# board.net
KiCad netlist of a schematic drawn in EAGLE
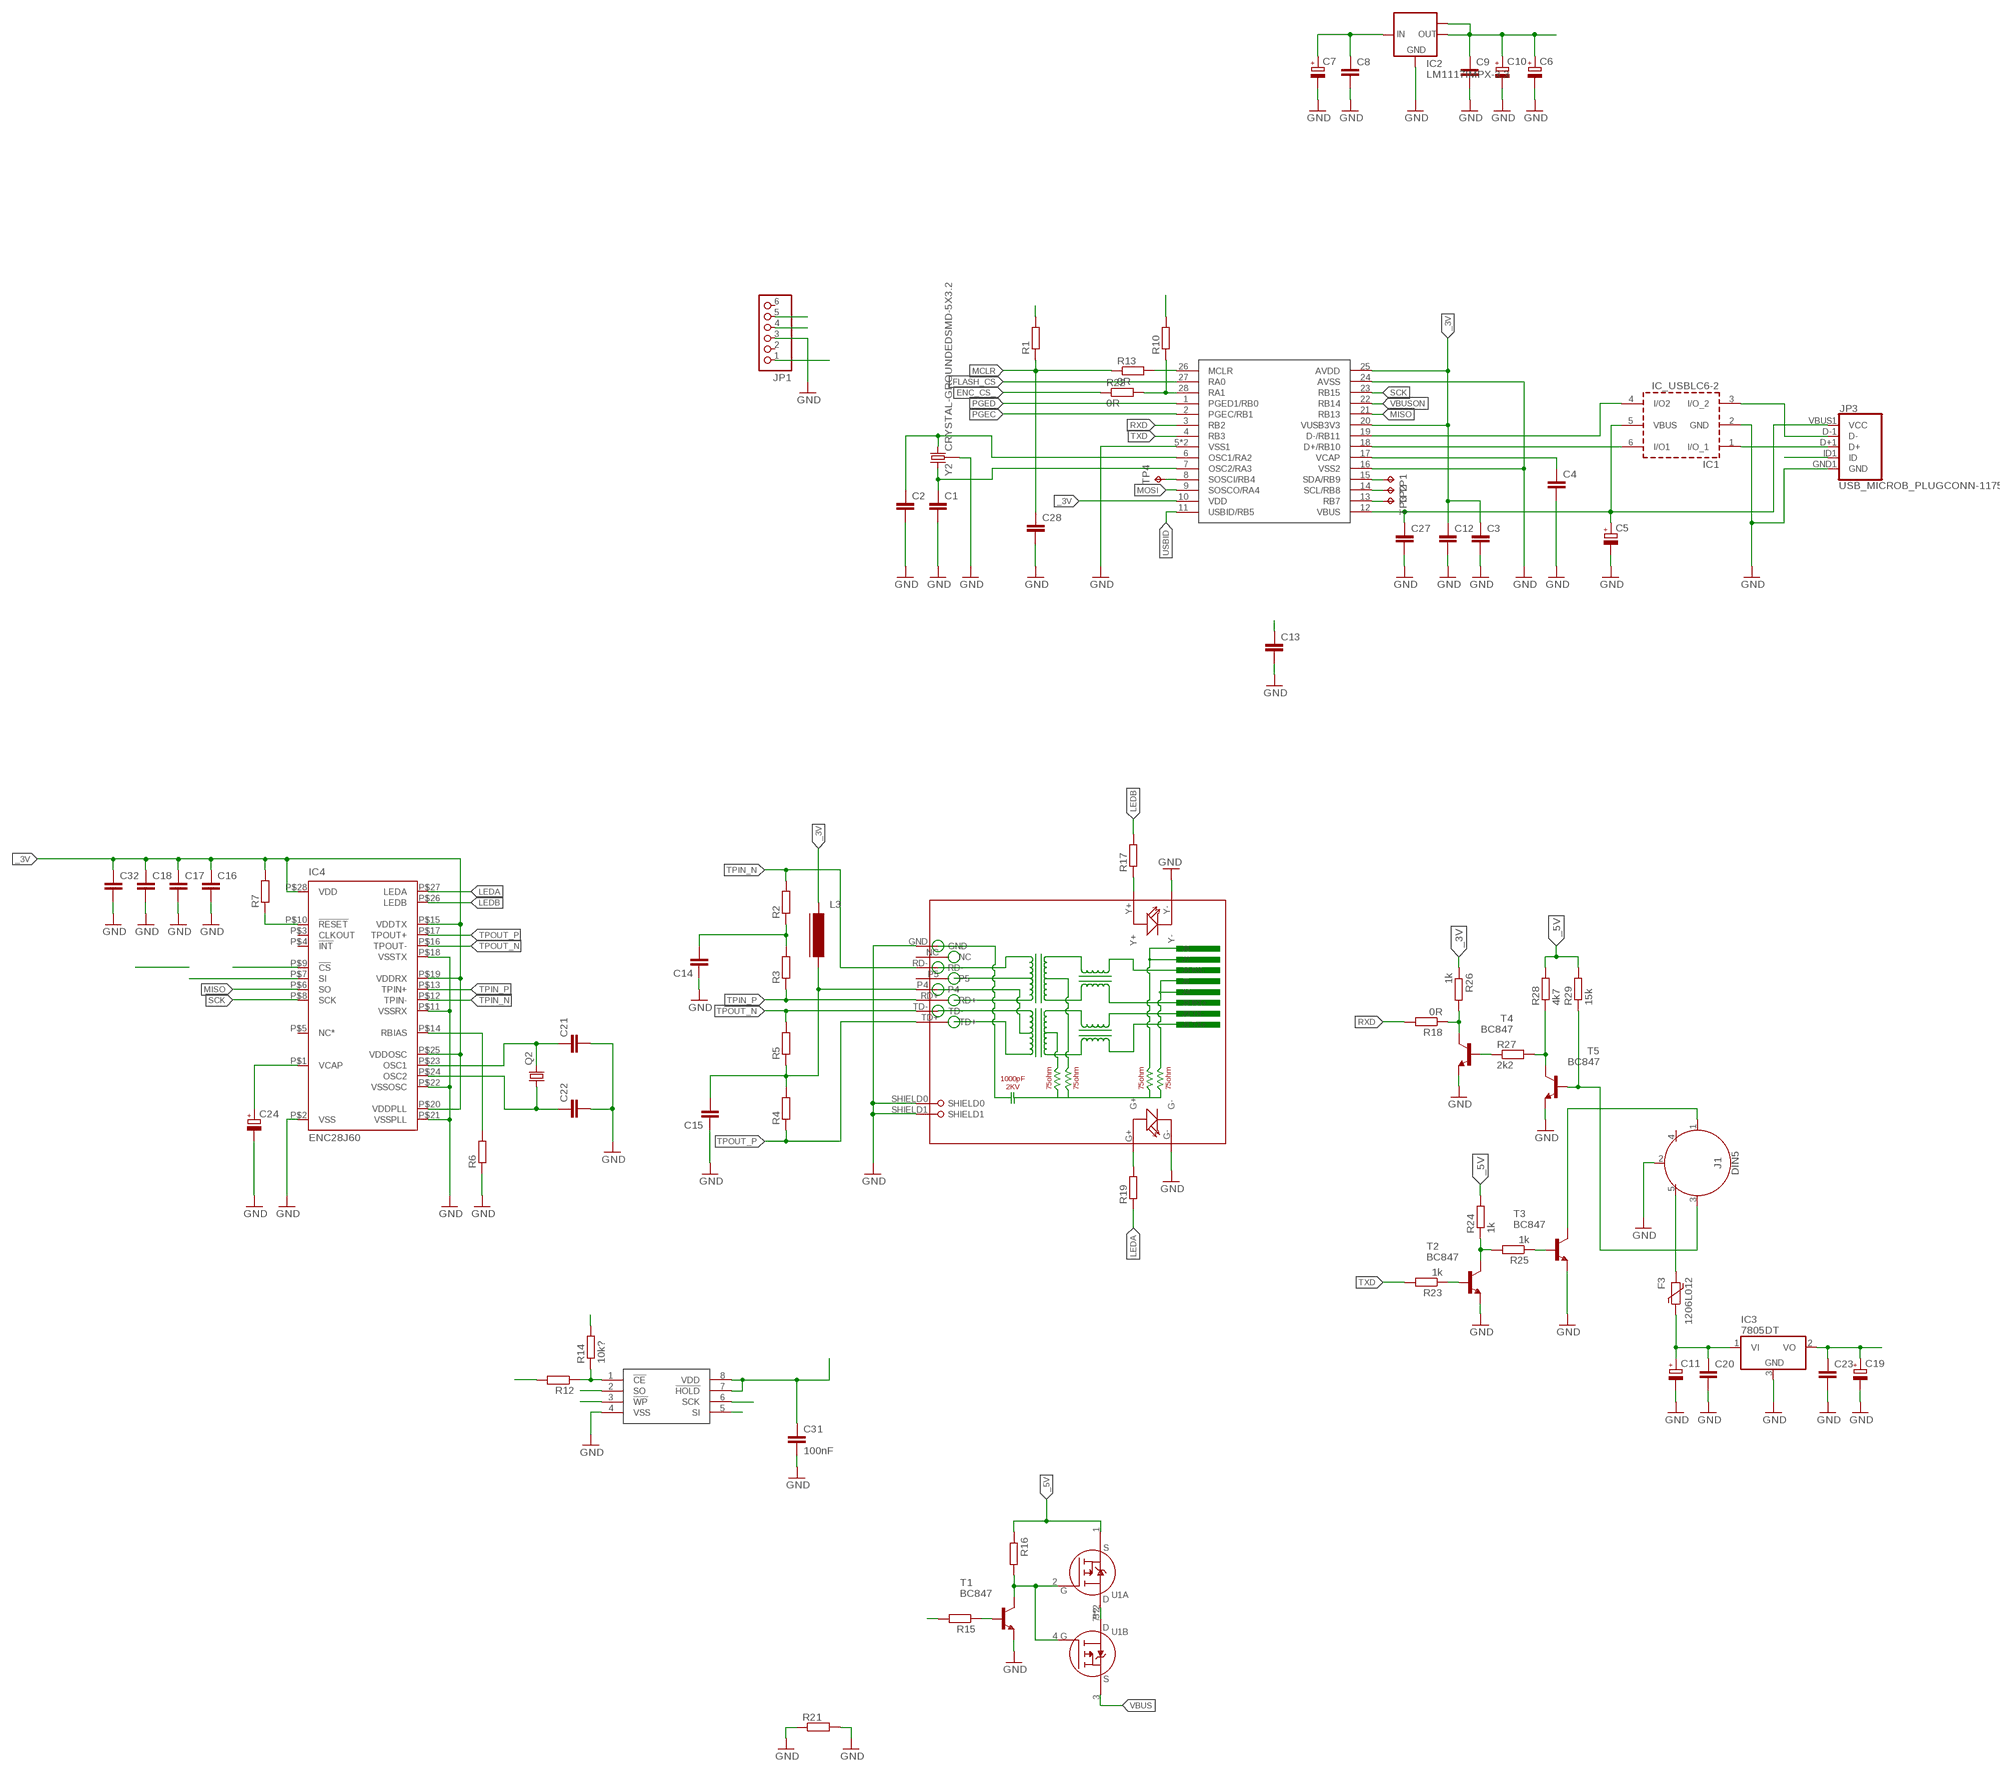
[diagram p0: schematic, sheet 1]

(export (version "E")
  (design (tool "Eeschema 10.0.6"))
  (components
    (comp (ref "C1")
      (value "C-EUC0603")
      (footprint "eagle-import:C0603")
      (libsource (lib "eagle-import") (part "C-EUC0603"))
    )
    (comp (ref "C2")
      (value "C-EUC0603")
      (footprint "eagle-import:C0603")
      (libsource (lib "eagle-import") (part "C-EUC0603"))
    )
    (comp (ref "C3")
      (value "C-EUC0402")
      (footprint "eagle-import:C0402")
      (libsource (lib "eagle-import") (part "C-EUC0402"))
    )
    (comp (ref "C4")
      (value "C-EUC0603")
      (footprint "eagle-import:C0603")
      (libsource (lib "eagle-import") (part "C-EUC0603"))
    )
    (comp (ref "C5")
      (value "CPOL-EUSMCA")
      (footprint "eagle-import:SMC_A")
      (libsource (lib "eagle-import") (part "CPOL-EUSMCA"))
    )
    (comp (ref "C6")
      (value "CPOL-EUSMCA")
      (footprint "eagle-import:SMC_A")
      (libsource (lib "eagle-import") (part "CPOL-EUSMCA"))
    )
    (comp (ref "C7")
      (value "CPOL-EUSMCC")
      (footprint "eagle-import:SMC_C")
      (libsource (lib "eagle-import") (part "CPOL-EUSMCC"))
    )
    (comp (ref "C8")
      (value "C-EUC0603")
      (footprint "eagle-import:C0603")
      (libsource (lib "eagle-import") (part "C-EUC0603"))
    )
    (comp (ref "C9")
      (value "C-EUC0603")
      (footprint "eagle-import:C0603")
      (libsource (lib "eagle-import") (part "C-EUC0603"))
    )
    (comp (ref "C10")
      (value "CPOL-EUSMCB")
      (footprint "eagle-import:SMC_B")
      (libsource (lib "eagle-import") (part "CPOL-EUSMCB"))
    )
    (comp (ref "C11")
      (value "CPOL-EUSMCC")
      (footprint "eagle-import:SMC_C")
      (libsource (lib "eagle-import") (part "CPOL-EUSMCC"))
    )
    (comp (ref "C12")
      (value "C-EUC0603")
      (footprint "eagle-import:C0603")
      (libsource (lib "eagle-import") (part "C-EUC0603"))
    )
    (comp (ref "C13")
      (value "C-EUC0603")
      (footprint "eagle-import:C0603")
      (libsource (lib "eagle-import") (part "C-EUC0603"))
    )
    (comp (ref "C14")
      (value "C-EUC0603")
      (footprint "eagle-import:C0603")
      (libsource (lib "eagle-import") (part "C-EUC0603"))
    )
    (comp (ref "C15")
      (value "C-EUC0603")
      (footprint "eagle-import:C0603")
      (libsource (lib "eagle-import") (part "C-EUC0603"))
    )
    (comp (ref "C16")
      (value "C-EUC0402")
      (footprint "eagle-import:C0402")
      (libsource (lib "eagle-import") (part "C-EUC0402"))
    )
    (comp (ref "C17")
      (value "C-EUC0402")
      (footprint "eagle-import:C0402")
      (libsource (lib "eagle-import") (part "C-EUC0402"))
    )
    (comp (ref "C18")
      (value "C-EUC0402")
      (footprint "eagle-import:C0402")
      (libsource (lib "eagle-import") (part "C-EUC0402"))
    )
    (comp (ref "C19")
      (value "CPOL-EUSMCC")
      (footprint "eagle-import:SMC_C")
      (libsource (lib "eagle-import") (part "CPOL-EUSMCC"))
    )
    (comp (ref "C20")
      (value "C-EUC0603")
      (footprint "eagle-import:C0603")
      (libsource (lib "eagle-import") (part "C-EUC0603"))
    )
    (comp (ref "C21")
      (value "C-EUC0603")
      (footprint "eagle-import:C0603")
      (libsource (lib "eagle-import") (part "C-EUC0603"))
    )
    (comp (ref "C22")
      (value "C-EUC0603")
      (footprint "eagle-import:C0603")
      (libsource (lib "eagle-import") (part "C-EUC0603"))
    )
    (comp (ref "C23")
      (value "C-EUC0603")
      (footprint "eagle-import:C0603")
      (libsource (lib "eagle-import") (part "C-EUC0603"))
    )
    (comp (ref "C24")
      (value "CPOL-EUSMCA")
      (footprint "eagle-import:SMC_A")
      (libsource (lib "eagle-import") (part "CPOL-EUSMCA"))
    )
    (comp (ref "C27")
      (value "C-EUC0603")
      (footprint "eagle-import:C0603")
      (libsource (lib "eagle-import") (part "C-EUC0603"))
    )
    (comp (ref "C28")
      (value "C-EUC0603")
      (footprint "eagle-import:C0603")
      (libsource (lib "eagle-import") (part "C-EUC0603"))
    )
    (comp (ref "C31")
      (value "100nF")
      (footprint "eagle-import:C0603")
      (libsource (lib "eagle-import") (part "C-EUC0603"))
    )
    (comp (ref "C32")
      (value "C-EUC0402")
      (footprint "eagle-import:C0402")
      (libsource (lib "eagle-import") (part "C-EUC0402"))
    )
    (comp (ref "F3")
      (value "1206L012")
      (footprint "eagle-import:1206L")
      (fields (field (name "MF") "Littelfuse"))
      (libsource (lib "eagle-import") (part "?1206L012"))
    )
    (comp (ref "IC1")
      (value "IC_USBLC6-2")
      (footprint "eagle-import:SOT-23-6L")
      (libsource (lib "eagle-import") (part "IC_USBLC6-2"))
    )
    (comp (ref "IC2")
      (value "LM1117IMPX-3.3")
      (footprint "eagle-import:SOT223")
      (libsource (lib "eagle-import") (part "LM1117IMPX-3.3"))
    )
    (comp (ref "IC3")
      (value "7805DT")
      (footprint "eagle-import:TO252")
      (libsource (lib "eagle-import") (part "78DT05"))
    )
    (comp (ref "IC4")
      (value "ENC28J60")
      (footprint "eagle-import:TSSOP28W")
      (libsource (lib "eagle-import") (part "ENC28J60"))
    )
    (comp (ref "J1")
      (value "DIN5")
      (footprint "eagle-import:DIN5-RA-PTH")
      (libsource (lib "eagle-import") (part "DIN5"))
    )
    (comp (ref "JP1")
      (value "PINHD-1X6")
      (footprint "eagle-import:1X06")
      (libsource (lib "eagle-import") (part "PINHD-1X6"))
    )
    (comp (ref "JP3")
      (value "USB_MICROB_PLUGCONN-11752")
      (footprint "eagle-import:USB-B-MICRO-SMD_V03")
      (libsource (lib "eagle-import") (part "USB_MICROB_PLUGCONN-11752"))
    )
    (comp (ref "L3")
      (value "FERRITE-0805")
      (footprint "eagle-import:FB805")
      (libsource (lib "eagle-import") (part "FERRITE-0805"))
    )
    (comp (ref "Q2")
      (value "CRYSTALHC49S")
      (footprint "eagle-import:HC49_S")
      (libsource (lib "eagle-import") (part "CRYSTALHC49S"))
    )
    (comp (ref "R1")
      (value "R-EU_R0603")
      (footprint "eagle-import:R0603")
      (libsource (lib "eagle-import") (part "R-EU_R0603"))
    )
    (comp (ref "R2")
      (value "R-EU_R0603")
      (footprint "eagle-import:R0603")
      (libsource (lib "eagle-import") (part "R-EU_R0603"))
    )
    (comp (ref "R3")
      (value "R-EU_R0603")
      (footprint "eagle-import:R0603")
      (libsource (lib "eagle-import") (part "R-EU_R0603"))
    )
    (comp (ref "R4")
      (value "R-EU_R0603")
      (footprint "eagle-import:R0603")
      (libsource (lib "eagle-import") (part "R-EU_R0603"))
    )
    (comp (ref "R5")
      (value "R-EU_R0603")
      (footprint "eagle-import:R0603")
      (libsource (lib "eagle-import") (part "R-EU_R0603"))
    )
    (comp (ref "R6")
      (value "R-EU_R0805")
      (footprint "eagle-import:R0805")
      (libsource (lib "eagle-import") (part "R-EU_R0805"))
    )
    (comp (ref "R7")
      (value "R-EU_R0603")
      (footprint "eagle-import:R0603")
      (libsource (lib "eagle-import") (part "R-EU_R0603"))
    )
    (comp (ref "R10")
      (value "R-EU_R0603")
      (footprint "eagle-import:R0603")
      (libsource (lib "eagle-import") (part "R-EU_R0603"))
    )
    (comp (ref "R12")
      (value "R-EU_R0603")
      (footprint "eagle-import:R0603")
      (libsource (lib "eagle-import") (part "R-EU_R0603"))
    )
    (comp (ref "R13")
      (value "0R")
      (footprint "eagle-import:R0603")
      (libsource (lib "eagle-import") (part "R-EU_R0603"))
    )
    (comp (ref "R14")
      (value "10k?")
      (footprint "eagle-import:R0603")
      (libsource (lib "eagle-import") (part "R-EU_R0603"))
    )
    (comp (ref "R15")
      (value "R-EU_R0603")
      (footprint "eagle-import:R0603")
      (libsource (lib "eagle-import") (part "R-EU_R0603"))
    )
    (comp (ref "R16")
      (value "R-EU_R0402")
      (footprint "eagle-import:R0402")
      (libsource (lib "eagle-import") (part "R-EU_R0402"))
    )
    (comp (ref "R17")
      (value "R-EU_R1206")
      (footprint "eagle-import:R1206")
      (libsource (lib "eagle-import") (part "R-EU_R1206"))
    )
    (comp (ref "R18")
      (value "0R")
      (footprint "eagle-import:R1206")
      (libsource (lib "eagle-import") (part "R-EU_R1206"))
    )
    (comp (ref "R19")
      (value "R-EU_R1206")
      (footprint "eagle-import:R1206")
      (libsource (lib "eagle-import") (part "R-EU_R1206"))
    )
    (comp (ref "R21")
      (value "R-EU_R1206")
      (footprint "eagle-import:R1206")
      (libsource (lib "eagle-import") (part "R-EU_R1206"))
    )
    (comp (ref "R22")
      (value "0R")
      (footprint "eagle-import:R0603")
      (libsource (lib "eagle-import") (part "R-EU_R0603"))
    )
    (comp (ref "R23")
      (value "1k")
      (footprint "eagle-import:R1206")
      (libsource (lib "eagle-import") (part "R-EU_R1206"))
    )
    (comp (ref "R24")
      (value "1k")
      (footprint "eagle-import:R0603")
      (libsource (lib "eagle-import") (part "R-EU_R0603"))
    )
    (comp (ref "R25")
      (value "1k")
      (footprint "eagle-import:R0603")
      (libsource (lib "eagle-import") (part "R-EU_R0603"))
    )
    (comp (ref "R26")
      (value "1k")
      (footprint "eagle-import:R0603")
      (libsource (lib "eagle-import") (part "R-EU_R0603"))
    )
    (comp (ref "R27")
      (value "2k2")
      (footprint "eagle-import:R0603")
      (libsource (lib "eagle-import") (part "R-EU_R0603"))
    )
    (comp (ref "R28")
      (value "4k7")
      (footprint "eagle-import:R0603")
      (libsource (lib "eagle-import") (part "R-EU_R0603"))
    )
    (comp (ref "R29")
      (value "15k")
      (footprint "eagle-import:R0603")
      (libsource (lib "eagle-import") (part "R-EU_R0603"))
    )
    (comp (ref "RJ1")
      (value "HR911105A")
      (footprint "eagle-import:HR911105A")
      (libsource (lib "eagle-import") (part "HR911105A"))
    )
    (comp (ref "T1")
      (value "BC847")
      (footprint "eagle-import:SOT23")
      (libsource (lib "eagle-import") (part "BC847"))
    )
    (comp (ref "T2")
      (value "BC847")
      (footprint "eagle-import:SOT23")
      (libsource (lib "eagle-import") (part "BC847"))
    )
    (comp (ref "T3")
      (value "BC847")
      (footprint "eagle-import:SOT23")
      (libsource (lib "eagle-import") (part "BC847"))
    )
    (comp (ref "T4")
      (value "BC847")
      (footprint "eagle-import:SOT23")
      (libsource (lib "eagle-import") (part "BC847"))
    )
    (comp (ref "T5")
      (value "BC847")
      (footprint "eagle-import:SOT23")
      (libsource (lib "eagle-import") (part "BC847"))
    )
    (comp (ref "TP1")
      (value "TPTP16R")
      (footprint "eagle-import:TP16R")
      (libsource (lib "eagle-import") (part "TPTP16R"))
    )
    (comp (ref "TP2")
      (value "TPTP16R")
      (footprint "eagle-import:TP16R")
      (libsource (lib "eagle-import") (part "TPTP16R"))
    )
    (comp (ref "TP3")
      (value "TPTP16R")
      (footprint "eagle-import:TP16R")
      (libsource (lib "eagle-import") (part "TPTP16R"))
    )
    (comp (ref "TP4")
      (value "TPTP16R")
      (footprint "eagle-import:TP16R")
      (libsource (lib "eagle-import") (part "TPTP16R"))
    )
    (comp (ref "U$1")
      (value "PIC32MX250F128B")
      (footprint "eagle-import:QFN-S28-6X6")
      (libsource (lib "eagle-import") (part "PIC32MX250F128B"))
    )
    (comp (ref "U$2")
      (value "SST25VF016BSO8M")
      (footprint "eagle-import:SO-08M")
      (libsource (lib "eagle-import") (part "SST25VF016BSO8M"))
    )
    (comp (ref "U1")
      (value "IRF7314_P_MOSFET")
      (footprint "eagle-import:SO-8")
      (libsource (lib "eagle-import") (part "IRF7314_P_MOSFET"))
    )
    (comp (ref "Y2")
      (value "CRYSTAL-GROUNDEDSMD-5X3.2")
      (footprint "eagle-import:CRYSTAL-SMD-5X3.2-4PAD")
      (libsource (lib "eagle-import") (part "CRYSTAL-GROUNDEDSMD-5X3.2"))
    )
  )
  (nets
    (net (code "1") (name "ENC_CS_") (class "Default")
      (node (ref "IC4") (pin "P$9") (pinfunction "~{CS}_P$9") (pintype "input"))
      (node (ref "R22") (pin "1") (pinfunction "1_1") (pintype "passive"))
    )
    (net (code "2") (name "FLASH_CS") (class "Default")
      (node (ref "R12") (pin "2") (pinfunction "2_2") (pintype "passive"))
      (node (ref "U$1") (pin "27") (pinfunction "RA0_27") (pintype "bidirectional"))
    )
    (net (code "3") (name "GND") (class "Default")
      (node (ref "C1") (pin "2") (pinfunction "2_2") (pintype "passive"))
      (node (ref "C10") (pin "-") (pinfunction "-_-") (pintype "passive"))
      (node (ref "C11") (pin "-") (pinfunction "-_-") (pintype "passive"))
      (node (ref "C12") (pin "2") (pinfunction "2_2") (pintype "passive"))
      (node (ref "C13") (pin "2") (pinfunction "2_2") (pintype "passive"))
      (node (ref "C14") (pin "1") (pinfunction "1_1") (pintype "passive"))
      (node (ref "C15") (pin "1") (pinfunction "1_1") (pintype "passive"))
      (node (ref "C16") (pin "2") (pinfunction "2_2") (pintype "passive"))
      (node (ref "C17") (pin "2") (pinfunction "2_2") (pintype "passive"))
      (node (ref "C18") (pin "2") (pinfunction "2_2") (pintype "passive"))
      (node (ref "C19") (pin "-") (pinfunction "-_-") (pintype "passive"))
      (node (ref "C2") (pin "2") (pinfunction "2_2") (pintype "passive"))
      (node (ref "C20") (pin "2") (pinfunction "2_2") (pintype "passive"))
      (node (ref "C21") (pin "2") (pinfunction "2_2") (pintype "passive"))
      (node (ref "C22") (pin "2") (pinfunction "2_2") (pintype "passive"))
      (node (ref "C23") (pin "2") (pinfunction "2_2") (pintype "passive"))
      (node (ref "C24") (pin "-") (pinfunction "-_-") (pintype "passive"))
      (node (ref "C27") (pin "2") (pinfunction "2_2") (pintype "passive"))
      (node (ref "C28") (pin "2") (pinfunction "2_2") (pintype "passive"))
      (node (ref "C3") (pin "2") (pinfunction "2_2") (pintype "passive"))
      (node (ref "C31") (pin "2") (pinfunction "2_2") (pintype "passive"))
      (node (ref "C32") (pin "2") (pinfunction "2_2") (pintype "passive"))
      (node (ref "C4") (pin "2") (pinfunction "2_2") (pintype "passive"))
      (node (ref "C5") (pin "-") (pinfunction "-_-") (pintype "passive"))
      (node (ref "C6") (pin "-") (pinfunction "-_-") (pintype "passive"))
      (node (ref "C7") (pin "-") (pinfunction "-_-") (pintype "passive"))
      (node (ref "C8") (pin "2") (pinfunction "2_2") (pintype "passive"))
      (node (ref "C9") (pin "2") (pinfunction "2_2") (pintype "passive"))
      (node (ref "IC1") (pin "2") (pinfunction "GND_2") (pintype "bidirectional"))
      (node (ref "IC2") (pin "1") (pinfunction "GND_1") (pintype "input"))
      (node (ref "IC3") (pin "3") (pinfunction "GND_3") (pintype "passive"))
      (node (ref "IC4") (pin "P$11") (pinfunction "VSSRX_P$11") (pintype "input"))
      (node (ref "IC4") (pin "P$18") (pinfunction "VSSTX_P$18") (pintype "input"))
      (node (ref "IC4") (pin "P$2") (pinfunction "VSS_P$2") (pintype "input"))
      (node (ref "IC4") (pin "P$21") (pinfunction "VSSPLL_P$21") (pintype "input"))
      (node (ref "IC4") (pin "P$22") (pinfunction "VSSOSC_P$22") (pintype "input"))
      (node (ref "J1") (pin "2") (pinfunction "2_2") (pintype "bidirectional"))
      (node (ref "JP1") (pin "3") (pinfunction "3_3") (pintype "passive"))
      (node (ref "JP3") (pin "GND1") (pinfunction "GND_GND1") (pintype "bidirectional"))
      (node (ref "R21") (pin "1") (pinfunction "1_1") (pintype "passive"))
      (node (ref "R21") (pin "2") (pinfunction "2_2") (pintype "passive"))
      (node (ref "R6") (pin "1") (pinfunction "1_1") (pintype "passive"))
      (node (ref "RJ1") (pin "G-") (pinfunction "G-_G-") (pintype "bidirectional"))
      (node (ref "RJ1") (pin "GND") (pinfunction "GND_GND") (pintype "bidirectional"))
      (node (ref "RJ1") (pin "SHIELD0") (pinfunction "SHIELD0_SHIELD0") (pintype "bidirectional"))
      (node (ref "RJ1") (pin "SHIELD1") (pinfunction "SHIELD1_SHIELD1") (pintype "bidirectional"))
      (node (ref "RJ1") (pin "Y-") (pinfunction "Y-_Y-") (pintype "bidirectional"))
      (node (ref "T1") (pin "2") (pinfunction "E_2") (pintype "passive"))
      (node (ref "T2") (pin "2") (pinfunction "E_2") (pintype "passive"))
      (node (ref "T3") (pin "2") (pinfunction "E_2") (pintype "passive"))
      (node (ref "T4") (pin "2") (pinfunction "E_2") (pintype "passive"))
      (node (ref "T5") (pin "2") (pinfunction "E_2") (pintype "passive"))
      (node (ref "U$1") (pin "16") (pinfunction "VSS2_16") (pintype "bidirectional"))
      (node (ref "U$1") (pin "24") (pinfunction "AVSS_24") (pintype "bidirectional"))
      (node (ref "U$1") (pin "5") (pinfunction "VSS1_5") (pintype "bidirectional"))
      (node (ref "U$1") (pin "EXP") (pinfunction "VSS1_EXP") (pintype "bidirectional"))
      (node (ref "U$2") (pin "4") (pinfunction "VSS_4") (pintype "bidirectional"))
      (node (ref "Y2") (pin "2") (pinfunction "3_2") (pintype "passive"))
      (node (ref "Y2") (pin "4") (pinfunction "3_4") (pintype "passive"))
    )
    (net (code "4") (name "LEDA") (class "Default")
      (node (ref "IC4") (pin "P$27") (pinfunction "LEDA_P$27") (pintype "output"))
      (node (ref "R19") (pin "1") (pinfunction "1_1") (pintype "passive"))
    )
    (net (code "5") (name "LEDB") (class "Default")
      (node (ref "IC4") (pin "P$26") (pinfunction "LEDB_P$26") (pintype "output"))
      (node (ref "R17") (pin "2") (pinfunction "2_2") (pintype "passive"))
    )
    (net (code "6") (name "MCLR") (class "Default")
      (node (ref "C28") (pin "1") (pinfunction "1_1") (pintype "passive"))
      (node (ref "JP1") (pin "1") (pinfunction "1_1") (pintype "passive"))
      (node (ref "R1") (pin "1") (pinfunction "1_1") (pintype "passive"))
      (node (ref "R13") (pin "1") (pinfunction "1_1") (pintype "passive"))
    )
    (net (code "7") (name "MISO") (class "Default")
      (node (ref "IC4") (pin "P$6") (pinfunction "SO_P$6") (pintype "output"))
      (node (ref "U$1") (pin "21") (pinfunction "RB13_21") (pintype "bidirectional"))
      (node (ref "U$2") (pin "2") (pinfunction "SO_2") (pintype "bidirectional"))
    )
    (net (code "8") (name "MOSI") (class "Default")
      (node (ref "IC4") (pin "P$7") (pinfunction "SI_P$7") (pintype "input"))
      (node (ref "U$1") (pin "9") (pinfunction "SOSCO/RA4_9") (pintype "bidirectional"))
      (node (ref "U$2") (pin "5") (pinfunction "SI_5") (pintype "bidirectional"))
    )
    (net (code "9") (name "Net-(C14-Pad2)") (class "Default")
      (node (ref "C14") (pin "2") (pinfunction "2_2") (pintype "passive"))
      (node (ref "R2") (pin "1") (pinfunction "1_1") (pintype "passive"))
      (node (ref "R3") (pin "2") (pinfunction "2_2") (pintype "passive"))
    )
    (net (code "10") (name "Net-(C15-Pad2)") (class "Default")
      (node (ref "C15") (pin "2") (pinfunction "2_2") (pintype "passive"))
      (node (ref "L3") (pin "2") (pinfunction "2_2") (pintype "passive"))
      (node (ref "R4") (pin "2") (pinfunction "2_2") (pintype "passive"))
      (node (ref "R5") (pin "1") (pinfunction "1_1") (pintype "passive"))
      (node (ref "RJ1") (pin "P4") (pinfunction "P4_P4") (pintype "bidirectional"))
    )
    (net (code "11") (name "Net-(F3-Pad2)") (class "Default")
      (node (ref "F3") (pin "2") (pinfunction "2_2") (pintype "passive"))
      (node (ref "J1") (pin "5") (pinfunction "5_5") (pintype "bidirectional"))
    )
    (net (code "12") (name "Net-(IC1-I{slash}O1)") (class "Default")
      (node (ref "IC1") (pin "6") (pinfunction "I/O1_6") (pintype "bidirectional"))
      (node (ref "U$1") (pin "18") (pinfunction "D+/RB10_18") (pintype "bidirectional"))
    )
    (net (code "13") (name "Net-(IC1-I{slash}O2)") (class "Default")
      (node (ref "IC1") (pin "4") (pinfunction "I/O2_4") (pintype "bidirectional"))
      (node (ref "U$1") (pin "19") (pinfunction "D-/RB11_19") (pintype "bidirectional"))
    )
    (net (code "14") (name "Net-(IC1-I{slash}O_1)") (class "Default")
      (node (ref "IC1") (pin "1") (pinfunction "I/O_1_1") (pintype "bidirectional"))
      (node (ref "JP3") (pin "D+1") (pinfunction "D+_D+1") (pintype "bidirectional"))
    )
    (net (code "15") (name "Net-(IC1-I{slash}O_2)") (class "Default")
      (node (ref "IC1") (pin "3") (pinfunction "I/O_2_3") (pintype "bidirectional"))
      (node (ref "JP3") (pin "D-1") (pinfunction "D-_D-1") (pintype "bidirectional"))
    )
    (net (code "16") (name "Net-(IC3-VI)") (class "Default")
      (node (ref "C11") (pin "+") (pinfunction "+_+") (pintype "passive"))
      (node (ref "C20") (pin "1") (pinfunction "1_1") (pintype "passive"))
      (node (ref "F3") (pin "1") (pinfunction "1_1") (pintype "passive"))
      (node (ref "IC3") (pin "1") (pinfunction "VI_1") (pintype "input"))
    )
    (net (code "17") (name "Net-(IC4-OSC1)") (class "Default")
      (node (ref "C21") (pin "1") (pinfunction "1_1") (pintype "passive"))
      (node (ref "IC4") (pin "P$23") (pinfunction "OSC1_P$23") (pintype "input"))
      (node (ref "Q2") (pin "2") (pinfunction "2_2") (pintype "passive"))
    )
    (net (code "18") (name "Net-(IC4-OSC2)") (class "Default")
      (node (ref "C22") (pin "1") (pinfunction "1_1") (pintype "passive"))
      (node (ref "IC4") (pin "P$24") (pinfunction "OSC2_P$24") (pintype "output"))
      (node (ref "Q2") (pin "1") (pinfunction "1_1") (pintype "passive"))
    )
    (net (code "19") (name "Net-(IC4-RBIAS)") (class "Default")
      (node (ref "IC4") (pin "P$14") (pinfunction "RBIAS_P$14") (pintype "input"))
      (node (ref "R6") (pin "2") (pinfunction "2_2") (pintype "passive"))
    )
    (net (code "20") (name "Net-(IC4-VCAP)") (class "Default")
      (node (ref "C24") (pin "+") (pinfunction "+_+") (pintype "passive"))
      (node (ref "IC4") (pin "P$1") (pinfunction "VCAP_P$1") (pintype "input"))
    )
    (net (code "21") (name "Net-(IC4-~{RESET})") (class "Default")
      (node (ref "IC4") (pin "P$10") (pinfunction "~{RESET}_P$10") (pintype "input"))
      (node (ref "R7") (pin "1") (pinfunction "1_1") (pintype "passive"))
    )
    (net (code "22") (name "Net-(R17-Pad1)") (class "Default")
      (node (ref "R17") (pin "1") (pinfunction "1_1") (pintype "passive"))
      (node (ref "RJ1") (pin "Y+") (pinfunction "Y+_Y+") (pintype "bidirectional"))
    )
    (net (code "23") (name "Net-(R19-Pad2)") (class "Default")
      (node (ref "R19") (pin "2") (pinfunction "2_2") (pintype "passive"))
      (node (ref "RJ1") (pin "G+") (pinfunction "G+_G+") (pintype "bidirectional"))
    )
    (net (code "24") (name "Net-(T1-B)") (class "Default")
      (node (ref "R15") (pin "1") (pinfunction "1_1") (pintype "passive"))
      (node (ref "T1") (pin "1") (pinfunction "B_1") (pintype "passive"))
    )
    (net (code "25") (name "Net-(T1-C)") (class "Default")
      (node (ref "R16") (pin "2") (pinfunction "2_2") (pintype "passive"))
      (node (ref "T1") (pin "3") (pinfunction "C_3") (pintype "passive"))
      (node (ref "U1") (pin "2") (pinfunction "G_2") (pintype "bidirectional"))
      (node (ref "U1") (pin "4") (pinfunction "G_4") (pintype "bidirectional"))
    )
    (net (code "26") (name "Net-(T2-B)") (class "Default")
      (node (ref "R23") (pin "1") (pinfunction "1_1") (pintype "passive"))
      (node (ref "T2") (pin "1") (pinfunction "B_1") (pintype "passive"))
    )
    (net (code "27") (name "Net-(T2-C)") (class "Default")
      (node (ref "R24") (pin "1") (pinfunction "1_1") (pintype "passive"))
      (node (ref "R25") (pin "2") (pinfunction "2_2") (pintype "passive"))
      (node (ref "T2") (pin "3") (pinfunction "C_3") (pintype "passive"))
    )
    (net (code "28") (name "Net-(T3-B)") (class "Default")
      (node (ref "R25") (pin "1") (pinfunction "1_1") (pintype "passive"))
      (node (ref "T3") (pin "1") (pinfunction "B_1") (pintype "passive"))
    )
    (net (code "29") (name "Net-(T3-C)") (class "Default")
      (node (ref "J1") (pin "1") (pinfunction "1_1") (pintype "bidirectional"))
      (node (ref "T3") (pin "3") (pinfunction "C_3") (pintype "passive"))
    )
    (net (code "30") (name "Net-(T4-B)") (class "Default")
      (node (ref "R27") (pin "1") (pinfunction "1_1") (pintype "passive"))
      (node (ref "T4") (pin "1") (pinfunction "B_1") (pintype "passive"))
    )
    (net (code "31") (name "Net-(T4-C)") (class "Default")
      (node (ref "R18") (pin "1") (pinfunction "1_1") (pintype "passive"))
      (node (ref "R26") (pin "2") (pinfunction "2_2") (pintype "passive"))
      (node (ref "T4") (pin "3") (pinfunction "C_3") (pintype "passive"))
    )
    (net (code "32") (name "Net-(T5-B)") (class "Default")
      (node (ref "J1") (pin "3") (pinfunction "3_3") (pintype "bidirectional"))
      (node (ref "R29") (pin "1") (pinfunction "1_1") (pintype "passive"))
      (node (ref "T5") (pin "1") (pinfunction "B_1") (pintype "passive"))
    )
    (net (code "33") (name "Net-(T5-C)") (class "Default")
      (node (ref "R27") (pin "2") (pinfunction "2_2") (pintype "passive"))
      (node (ref "R28") (pin "1") (pinfunction "1_1") (pintype "passive"))
      (node (ref "T5") (pin "3") (pinfunction "C_3") (pintype "passive"))
    )
    (net (code "34") (name "Net-(U$1-MCLR)") (class "Default")
      (node (ref "R13") (pin "2") (pinfunction "2_2") (pintype "passive"))
      (node (ref "U$1") (pin "26") (pinfunction "MCLR_26") (pintype "bidirectional"))
    )
    (net (code "35") (name "Net-(U$1-OSC1{slash}RA2)") (class "Default")
      (node (ref "C2") (pin "1") (pinfunction "1_1") (pintype "passive"))
      (node (ref "U$1") (pin "6") (pinfunction "OSC1/RA2_6") (pintype "bidirectional"))
      (node (ref "Y2") (pin "1") (pinfunction "2_1") (pintype "passive"))
    )
    (net (code "36") (name "Net-(U$1-OSC2{slash}RA3)") (class "Default")
      (node (ref "C1") (pin "1") (pinfunction "1_1") (pintype "passive"))
      (node (ref "U$1") (pin "7") (pinfunction "OSC2/RA3_7") (pintype "bidirectional"))
      (node (ref "Y2") (pin "3") (pinfunction "1_3") (pintype "passive"))
    )
    (net (code "37") (name "Net-(U$1-RA1)") (class "Default")
      (node (ref "R10") (pin "1") (pinfunction "1_1") (pintype "passive"))
      (node (ref "R22") (pin "2") (pinfunction "2_2") (pintype "passive"))
      (node (ref "U$1") (pin "28") (pinfunction "RA1_28") (pintype "bidirectional"))
    )
    (net (code "38") (name "Net-(U$1-RB7)") (class "Default")
      (node (ref "TP3") (pin "TP") (pinfunction "TP_TP") (pintype "input"))
      (node (ref "U$1") (pin "13") (pinfunction "RB7_13") (pintype "bidirectional"))
    )
    (net (code "39") (name "Net-(U$1-SCL{slash}RB8)") (class "Default")
      (node (ref "TP2") (pin "TP") (pinfunction "TP_TP") (pintype "input"))
      (node (ref "U$1") (pin "14") (pinfunction "SCL/RB8_14") (pintype "bidirectional"))
    )
    (net (code "40") (name "Net-(U$1-SDA{slash}RB9)") (class "Default")
      (node (ref "TP1") (pin "TP") (pinfunction "TP_TP") (pintype "input"))
      (node (ref "U$1") (pin "15") (pinfunction "SDA/RB9_15") (pintype "bidirectional"))
    )
    (net (code "41") (name "Net-(U$1-SOSCI{slash}RB4)") (class "Default")
      (node (ref "TP4") (pin "TP") (pinfunction "TP_TP") (pintype "input"))
      (node (ref "U$1") (pin "8") (pinfunction "SOSCI/RB4_8") (pintype "bidirectional"))
    )
    (net (code "42") (name "Net-(U$1-VCAP)") (class "Default")
      (node (ref "C4") (pin "1") (pinfunction "1_1") (pintype "passive"))
      (node (ref "U$1") (pin "17") (pinfunction "VCAP_17") (pintype "bidirectional"))
    )
    (net (code "43") (name "Net-(U$2-~{CE})") (class "Default")
      (node (ref "R12") (pin "1") (pinfunction "1_1") (pintype "passive"))
      (node (ref "R14") (pin "1") (pinfunction "1_1") (pintype "passive"))
      (node (ref "U$2") (pin "1") (pinfunction "~{CE}_1") (pintype "bidirectional"))
    )
    (net (code "44") (name "Net-(U1A-D-Pad7)") (class "Default")
      (node (ref "U1") (pin "5") (pinfunction "D_5") (pintype "bidirectional"))
      (node (ref "U1") (pin "6") (pinfunction "D_6") (pintype "bidirectional"))
      (node (ref "U1") (pin "7") (pinfunction "D_7") (pintype "bidirectional"))
      (node (ref "U1") (pin "8") (pinfunction "D_8") (pintype "bidirectional"))
    )
    (net (code "45") (name "PGEC") (class "Default")
      (node (ref "JP1") (pin "5") (pinfunction "5_5") (pintype "passive"))
      (node (ref "U$1") (pin "2") (pinfunction "PGEC/RB1_2") (pintype "bidirectional"))
    )
    (net (code "46") (name "PGED") (class "Default")
      (node (ref "JP1") (pin "4") (pinfunction "4_4") (pintype "passive"))
      (node (ref "U$1") (pin "1") (pinfunction "PGED1/RB0_1") (pintype "bidirectional"))
    )
    (net (code "47") (name "RXD") (class "Default")
      (node (ref "R18") (pin "2") (pinfunction "2_2") (pintype "passive"))
      (node (ref "U$1") (pin "3") (pinfunction "RB2_3") (pintype "bidirectional"))
    )
    (net (code "48") (name "SCK") (class "Default")
      (node (ref "IC4") (pin "P$8") (pinfunction "SCK_P$8") (pintype "input"))
      (node (ref "U$1") (pin "23") (pinfunction "RB15_23") (pintype "bidirectional"))
      (node (ref "U$2") (pin "6") (pinfunction "SCK_6") (pintype "bidirectional"))
    )
    (net (code "49") (name "TPIN_N") (class "Default")
      (node (ref "IC4") (pin "P$12") (pinfunction "TPIN-_P$12") (pintype "input"))
      (node (ref "R2") (pin "2") (pinfunction "2_2") (pintype "passive"))
      (node (ref "RJ1") (pin "RD-") (pinfunction "RD-_RD-") (pintype "bidirectional"))
    )
    (net (code "50") (name "TPIN_P") (class "Default")
      (node (ref "IC4") (pin "P$13") (pinfunction "TPIN+_P$13") (pintype "input"))
      (node (ref "R3") (pin "1") (pinfunction "1_1") (pintype "passive"))
      (node (ref "RJ1") (pin "RD+") (pinfunction "RD+_RD+") (pintype "bidirectional"))
    )
    (net (code "51") (name "TPOUT_N") (class "Default")
      (node (ref "IC4") (pin "P$16") (pinfunction "TPOUT-_P$16") (pintype "output"))
      (node (ref "R5") (pin "2") (pinfunction "2_2") (pintype "passive"))
      (node (ref "RJ1") (pin "TD-") (pinfunction "TD-_TD-") (pintype "bidirectional"))
    )
    (net (code "52") (name "TPOUT_P") (class "Default")
      (node (ref "IC4") (pin "P$17") (pinfunction "TPOUT+_P$17") (pintype "output"))
      (node (ref "R4") (pin "1") (pinfunction "1_1") (pintype "passive"))
      (node (ref "RJ1") (pin "TD+") (pinfunction "TD+_TD+") (pintype "bidirectional"))
    )
    (net (code "53") (name "TXD") (class "Default")
      (node (ref "R23") (pin "2") (pinfunction "2_2") (pintype "passive"))
      (node (ref "U$1") (pin "4") (pinfunction "RB3_4") (pintype "bidirectional"))
    )
    (net (code "54") (name "USBID") (class "Default")
      (node (ref "JP3") (pin "ID1") (pinfunction "ID_ID1") (pintype "bidirectional"))
      (node (ref "U$1") (pin "11") (pinfunction "USBID/RB5_11") (pintype "bidirectional"))
    )
    (net (code "55") (name "VBUS") (class "Default")
      (node (ref "C27") (pin "1") (pinfunction "1_1") (pintype "passive"))
      (node (ref "C5") (pin "+") (pinfunction "+_+") (pintype "passive"))
      (node (ref "IC1") (pin "5") (pinfunction "VBUS_5") (pintype "bidirectional"))
      (node (ref "JP3") (pin "VBUS1") (pinfunction "VCC_VBUS1") (pintype "bidirectional"))
      (node (ref "U$1") (pin "12") (pinfunction "VBUS_12") (pintype "bidirectional"))
      (node (ref "U1") (pin "3") (pinfunction "S_3") (pintype "bidirectional"))
    )
    (net (code "56") (name "VBUSON") (class "Default")
      (node (ref "R15") (pin "2") (pinfunction "2_2") (pintype "passive"))
      (node (ref "U$1") (pin "22") (pinfunction "RB14_22") (pintype "bidirectional"))
    )
    (net (code "57") (name "_3V") (class "Default")
      (node (ref "C10") (pin "+") (pinfunction "+_+") (pintype "passive"))
      (node (ref "C12") (pin "1") (pinfunction "1_1") (pintype "passive"))
      (node (ref "C13") (pin "1") (pinfunction "1_1") (pintype "passive"))
      (node (ref "C16") (pin "1") (pinfunction "1_1") (pintype "passive"))
      (node (ref "C17") (pin "1") (pinfunction "1_1") (pintype "passive"))
      (node (ref "C18") (pin "1") (pinfunction "1_1") (pintype "passive"))
      (node (ref "C3") (pin "1") (pinfunction "1_1") (pintype "passive"))
      (node (ref "C31") (pin "1") (pinfunction "1_1") (pintype "passive"))
      (node (ref "C32") (pin "1") (pinfunction "1_1") (pintype "passive"))
      (node (ref "C6") (pin "+") (pinfunction "+_+") (pintype "passive"))
      (node (ref "C9") (pin "1") (pinfunction "1_1") (pintype "passive"))
      (node (ref "IC2") (pin "2") (pinfunction "OUT_2") (pintype "passive"))
      (node (ref "IC2") (pin "TAB") (pinfunction "OUT1_TAB") (pintype "passive"))
      (node (ref "IC4") (pin "P$15") (pinfunction "VDDTX_P$15") (pintype "input"))
      (node (ref "IC4") (pin "P$19") (pinfunction "VDDRX_P$19") (pintype "input"))
      (node (ref "IC4") (pin "P$20") (pinfunction "VDDPLL_P$20") (pintype "input"))
      (node (ref "IC4") (pin "P$25") (pinfunction "VDDOSC_P$25") (pintype "input"))
      (node (ref "IC4") (pin "P$28") (pinfunction "VDD_P$28") (pintype "input"))
      (node (ref "L3") (pin "1") (pinfunction "1_1") (pintype "passive"))
      (node (ref "R1") (pin "2") (pinfunction "2_2") (pintype "passive"))
      (node (ref "R10") (pin "2") (pinfunction "2_2") (pintype "passive"))
      (node (ref "R14") (pin "2") (pinfunction "2_2") (pintype "passive"))
      (node (ref "R26") (pin "1") (pinfunction "1_1") (pintype "passive"))
      (node (ref "R7") (pin "2") (pinfunction "2_2") (pintype "passive"))
      (node (ref "U$1") (pin "10") (pinfunction "VDD_10") (pintype "bidirectional"))
      (node (ref "U$1") (pin "20") (pinfunction "VUSB3V3_20") (pintype "bidirectional"))
      (node (ref "U$1") (pin "25") (pinfunction "AVDD_25") (pintype "bidirectional"))
      (node (ref "U$2") (pin "3") (pinfunction "~{WP}_3") (pintype "bidirectional"))
      (node (ref "U$2") (pin "7") (pinfunction "~{HOLD}_7") (pintype "bidirectional"))
      (node (ref "U$2") (pin "8") (pinfunction "VDD_8") (pintype "bidirectional"))
    )
    (net (code "58") (name "_5V") (class "Default")
      (node (ref "C19") (pin "+") (pinfunction "+_+") (pintype "passive"))
      (node (ref "C23") (pin "1") (pinfunction "1_1") (pintype "passive"))
      (node (ref "C7") (pin "+") (pinfunction "+_+") (pintype "passive"))
      (node (ref "C8") (pin "1") (pinfunction "1_1") (pintype "passive"))
      (node (ref "IC2") (pin "3") (pinfunction "IN_3") (pintype "input"))
      (node (ref "IC3") (pin "2") (pinfunction "VO_2") (pintype "passive"))
      (node (ref "R16") (pin "1") (pinfunction "1_1") (pintype "passive"))
      (node (ref "R24") (pin "2") (pinfunction "2_2") (pintype "passive"))
      (node (ref "R28") (pin "2") (pinfunction "2_2") (pintype "passive"))
      (node (ref "R29") (pin "2") (pinfunction "2_2") (pintype "passive"))
      (node (ref "U1") (pin "1") (pinfunction "S_1") (pintype "bidirectional"))
    )
    (net (code "59") (name "unconnected-(IC4-CLKOUT-PadP$3)") (class "Default")
      (node (ref "IC4") (pin "P$3") (pinfunction "CLKOUT_P$3") (pintype "output"))
    )
    (net (code "60") (name "unconnected-(IC4-NC*-PadP$5)") (class "Default")
      (node (ref "IC4") (pin "P$5") (pinfunction "NC*_P$5") (pintype "output"))
    )
    (net (code "61") (name "unconnected-(IC4-~{INT}-PadP$4)") (class "Default")
      (node (ref "IC4") (pin "P$4") (pinfunction "~{INT}_P$4") (pintype "output"))
    )
    (net (code "62") (name "unconnected-(J1-Pad4)") (class "Default")
      (node (ref "J1") (pin "4") (pinfunction "4_4") (pintype "bidirectional"))
    )
    (net (code "63") (name "unconnected-(JP1-Pad2)") (class "Default")
      (node (ref "JP1") (pin "2") (pinfunction "2_2") (pintype "passive"))
    )
    (net (code "64") (name "unconnected-(JP1-Pad6)") (class "Default")
      (node (ref "JP1") (pin "6") (pinfunction "6_6") (pintype "passive"))
    )
    (net (code "65") (name "unconnected-(RJ1-PadNC)") (class "Default")
      (node (ref "RJ1") (pin "NC") (pinfunction "NC_NC") (pintype "bidirectional"))
    )
    (net (code "66") (name "unconnected-(RJ1-PadP5)") (class "Default")
      (node (ref "RJ1") (pin "P5") (pinfunction "P5_P5") (pintype "bidirectional"))
    )
  )
)
